# 16_ch_sample-and-hold_card.net
KiCad netlist of a schematic drawn in EAGLE
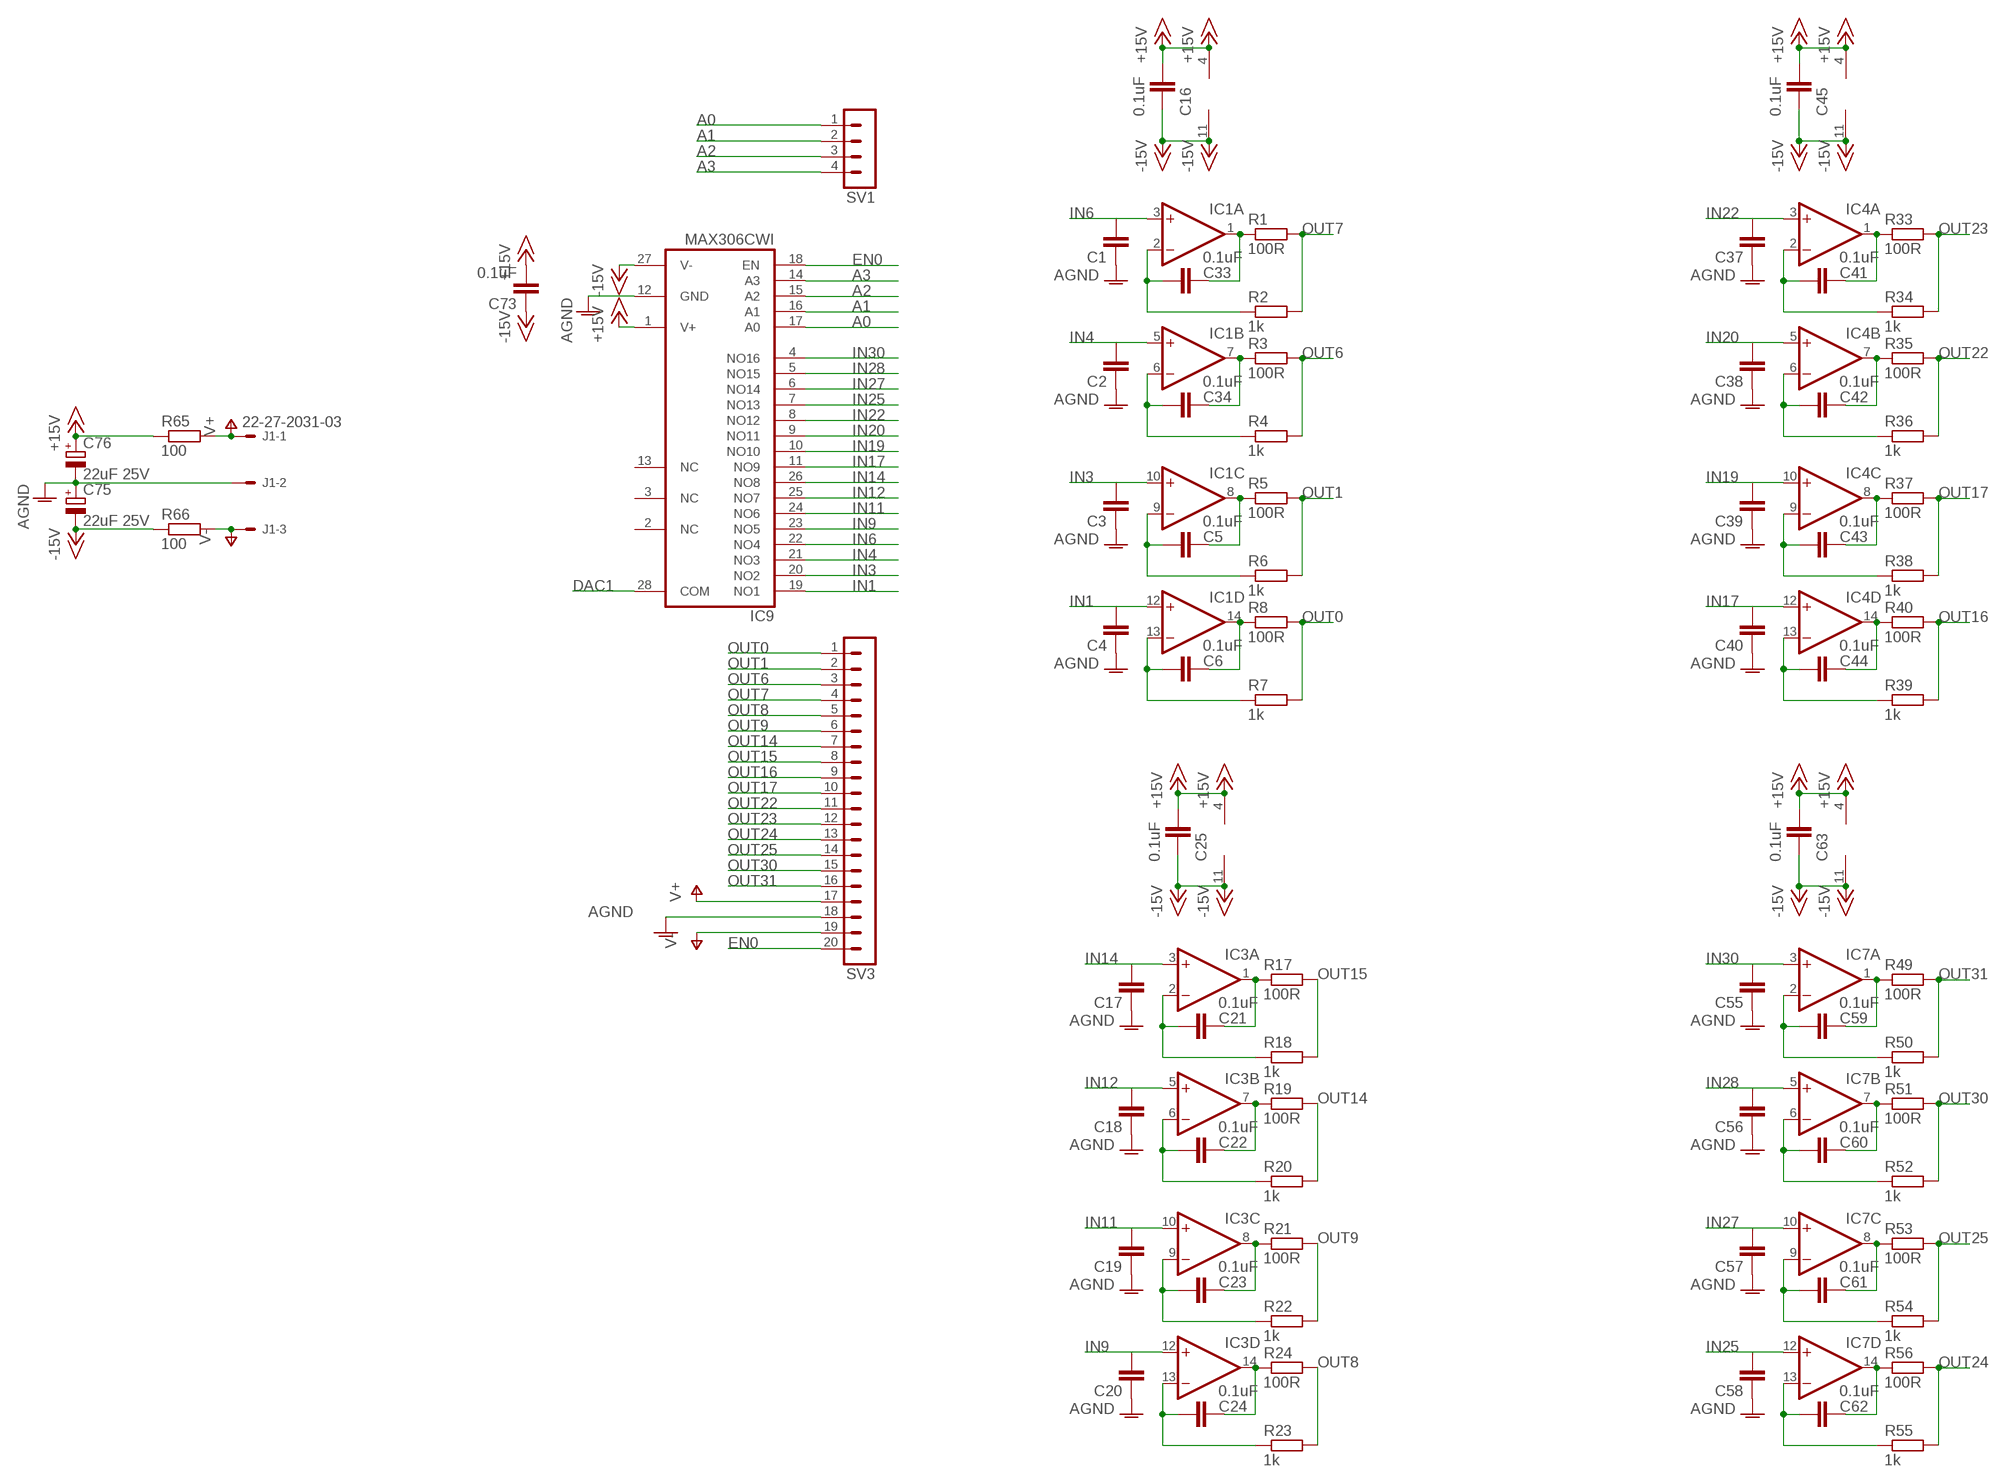
[diagram p0: schematic, sheet 1]

(export (version "E")
  (design (tool "Eeschema 10.0.6"))
  (components
    (comp (ref "C1")
      (value "C-EUC1206")
      (footprint "eagle-import:C1206")
      (libsource (lib "eagle-import") (part "C-EUC1206"))
    )
    (comp (ref "C2")
      (value "C-EUC1206")
      (footprint "eagle-import:C1206")
      (libsource (lib "eagle-import") (part "C-EUC1206"))
    )
    (comp (ref "C3")
      (value "C-EUC1206")
      (footprint "eagle-import:C1206")
      (libsource (lib "eagle-import") (part "C-EUC1206"))
    )
    (comp (ref "C4")
      (value "C-EUC1206")
      (footprint "eagle-import:C1206")
      (libsource (lib "eagle-import") (part "C-EUC1206"))
    )
    (comp (ref "C5")
      (value "0.1uF")
      (footprint "eagle-import:C0603")
      (libsource (lib "eagle-import") (part "C-EUC0603"))
    )
    (comp (ref "C6")
      (value "0.1uF")
      (footprint "eagle-import:C0603")
      (libsource (lib "eagle-import") (part "C-EUC0603"))
    )
    (comp (ref "C16")
      (value "0.1uF")
      (footprint "eagle-import:C0603")
      (libsource (lib "eagle-import") (part "C-EUC0603"))
    )
    (comp (ref "C17")
      (value "C-EUC1206")
      (footprint "eagle-import:C1206")
      (libsource (lib "eagle-import") (part "C-EUC1206"))
    )
    (comp (ref "C18")
      (value "C-EUC1206")
      (footprint "eagle-import:C1206")
      (libsource (lib "eagle-import") (part "C-EUC1206"))
    )
    (comp (ref "C19")
      (value "C-EUC1206")
      (footprint "eagle-import:C1206")
      (libsource (lib "eagle-import") (part "C-EUC1206"))
    )
    (comp (ref "C20")
      (value "C-EUC1206")
      (footprint "eagle-import:C1206")
      (libsource (lib "eagle-import") (part "C-EUC1206"))
    )
    (comp (ref "C21")
      (value "0.1uF")
      (footprint "eagle-import:C0603")
      (libsource (lib "eagle-import") (part "C-EUC0603"))
    )
    (comp (ref "C22")
      (value "0.1uF")
      (footprint "eagle-import:C0603")
      (libsource (lib "eagle-import") (part "C-EUC0603"))
    )
    (comp (ref "C23")
      (value "0.1uF")
      (footprint "eagle-import:C0603")
      (libsource (lib "eagle-import") (part "C-EUC0603"))
    )
    (comp (ref "C24")
      (value "0.1uF")
      (footprint "eagle-import:C0603")
      (libsource (lib "eagle-import") (part "C-EUC0603"))
    )
    (comp (ref "C25")
      (value "0.1uF")
      (footprint "eagle-import:C0603")
      (libsource (lib "eagle-import") (part "C-EUC0603"))
    )
    (comp (ref "C33")
      (value "0.1uF")
      (footprint "eagle-import:C0603")
      (libsource (lib "eagle-import") (part "C-EUC0603"))
    )
    (comp (ref "C34")
      (value "0.1uF")
      (footprint "eagle-import:C0603")
      (libsource (lib "eagle-import") (part "C-EUC0603"))
    )
    (comp (ref "C37")
      (value "C-EUC1206")
      (footprint "eagle-import:C1206")
      (libsource (lib "eagle-import") (part "C-EUC1206"))
    )
    (comp (ref "C38")
      (value "C-EUC1206")
      (footprint "eagle-import:C1206")
      (libsource (lib "eagle-import") (part "C-EUC1206"))
    )
    (comp (ref "C39")
      (value "C-EUC1206")
      (footprint "eagle-import:C1206")
      (libsource (lib "eagle-import") (part "C-EUC1206"))
    )
    (comp (ref "C40")
      (value "C-EUC1206")
      (footprint "eagle-import:C1206")
      (libsource (lib "eagle-import") (part "C-EUC1206"))
    )
    (comp (ref "C41")
      (value "0.1uF")
      (footprint "eagle-import:C0603")
      (libsource (lib "eagle-import") (part "C-EUC0603"))
    )
    (comp (ref "C42")
      (value "0.1uF")
      (footprint "eagle-import:C0603")
      (libsource (lib "eagle-import") (part "C-EUC0603"))
    )
    (comp (ref "C43")
      (value "0.1uF")
      (footprint "eagle-import:C0603")
      (libsource (lib "eagle-import") (part "C-EUC0603"))
    )
    (comp (ref "C44")
      (value "0.1uF")
      (footprint "eagle-import:C0603")
      (libsource (lib "eagle-import") (part "C-EUC0603"))
    )
    (comp (ref "C45")
      (value "0.1uF")
      (footprint "eagle-import:C0603")
      (libsource (lib "eagle-import") (part "C-EUC0603"))
    )
    (comp (ref "C55")
      (value "C-EUC1206")
      (footprint "eagle-import:C1206")
      (libsource (lib "eagle-import") (part "C-EUC1206"))
    )
    (comp (ref "C56")
      (value "C-EUC1206")
      (footprint "eagle-import:C1206")
      (libsource (lib "eagle-import") (part "C-EUC1206"))
    )
    (comp (ref "C57")
      (value "C-EUC1206")
      (footprint "eagle-import:C1206")
      (libsource (lib "eagle-import") (part "C-EUC1206"))
    )
    (comp (ref "C58")
      (value "C-EUC1206")
      (footprint "eagle-import:C1206")
      (libsource (lib "eagle-import") (part "C-EUC1206"))
    )
    (comp (ref "C59")
      (value "0.1uF")
      (footprint "eagle-import:C0603")
      (libsource (lib "eagle-import") (part "C-EUC0603"))
    )
    (comp (ref "C60")
      (value "0.1uF")
      (footprint "eagle-import:C0603")
      (libsource (lib "eagle-import") (part "C-EUC0603"))
    )
    (comp (ref "C61")
      (value "0.1uF")
      (footprint "eagle-import:C0603")
      (libsource (lib "eagle-import") (part "C-EUC0603"))
    )
    (comp (ref "C62")
      (value "0.1uF")
      (footprint "eagle-import:C0603")
      (libsource (lib "eagle-import") (part "C-EUC0603"))
    )
    (comp (ref "C63")
      (value "0.1uF")
      (footprint "eagle-import:C0603")
      (libsource (lib "eagle-import") (part "C-EUC0603"))
    )
    (comp (ref "C73")
      (value "0.1uF")
      (footprint "eagle-import:C0603")
      (libsource (lib "eagle-import") (part "C-EUC0603"))
    )
    (comp (ref "C75")
      (value "22uF 25V")
      (footprint "eagle-import:E2-5")
      (libsource (lib "eagle-import") (part "CPOL-EUE2-5"))
    )
    (comp (ref "C76")
      (value "22uF 25V")
      (footprint "eagle-import:E2-5")
      (libsource (lib "eagle-import") (part "CPOL-EUE2-5"))
    )
    (comp (ref "IC1")
      (value "TL074D")
      (footprint "eagle-import:SO14")
      (libsource (lib "eagle-import") (part "TL074D"))
    )
    (comp (ref "IC3")
      (value "TL074D")
      (footprint "eagle-import:SO14")
      (libsource (lib "eagle-import") (part "TL074D"))
    )
    (comp (ref "IC4")
      (value "TL074D")
      (footprint "eagle-import:SO14")
      (libsource (lib "eagle-import") (part "TL074D"))
    )
    (comp (ref "IC7")
      (value "TL074D")
      (footprint "eagle-import:SO14")
      (libsource (lib "eagle-import") (part "TL074D"))
    )
    (comp (ref "IC9")
      (value "MAX306CWI")
      (footprint "eagle-import:SO28L")
      (fields (field (name "MF") "MAXIM"))
      (libsource (lib "eagle-import") (part "MAX306CWI"))
    )
    (comp (ref "J1")
      (value "22-27-2031-03")
      (footprint "eagle-import:6410-03")
      (libsource (lib "eagle-import") (part "22-?-0327-2031"))
    )
    (comp (ref "R1")
      (value "100R")
      (footprint "eagle-import:R0603")
      (libsource (lib "eagle-import") (part "R-EU_R0603"))
    )
    (comp (ref "R2")
      (value "1k")
      (footprint "eagle-import:R0603")
      (libsource (lib "eagle-import") (part "R-EU_R0603"))
    )
    (comp (ref "R3")
      (value "100R")
      (footprint "eagle-import:R0603")
      (libsource (lib "eagle-import") (part "R-EU_R0603"))
    )
    (comp (ref "R4")
      (value "1k")
      (footprint "eagle-import:R0603")
      (libsource (lib "eagle-import") (part "R-EU_R0603"))
    )
    (comp (ref "R5")
      (value "100R")
      (footprint "eagle-import:R0603")
      (libsource (lib "eagle-import") (part "R-EU_R0603"))
    )
    (comp (ref "R6")
      (value "1k")
      (footprint "eagle-import:R0603")
      (libsource (lib "eagle-import") (part "R-EU_R0603"))
    )
    (comp (ref "R7")
      (value "1k")
      (footprint "eagle-import:R0603")
      (libsource (lib "eagle-import") (part "R-EU_R0603"))
    )
    (comp (ref "R8")
      (value "100R")
      (footprint "eagle-import:R0603")
      (libsource (lib "eagle-import") (part "R-EU_R0603"))
    )
    (comp (ref "R17")
      (value "100R")
      (footprint "eagle-import:R0603")
      (libsource (lib "eagle-import") (part "R-EU_R0603"))
    )
    (comp (ref "R18")
      (value "1k")
      (footprint "eagle-import:R0603")
      (libsource (lib "eagle-import") (part "R-EU_R0603"))
    )
    (comp (ref "R19")
      (value "100R")
      (footprint "eagle-import:R0603")
      (libsource (lib "eagle-import") (part "R-EU_R0603"))
    )
    (comp (ref "R20")
      (value "1k")
      (footprint "eagle-import:R0603")
      (libsource (lib "eagle-import") (part "R-EU_R0603"))
    )
    (comp (ref "R21")
      (value "100R")
      (footprint "eagle-import:R0603")
      (libsource (lib "eagle-import") (part "R-EU_R0603"))
    )
    (comp (ref "R22")
      (value "1k")
      (footprint "eagle-import:R0603")
      (libsource (lib "eagle-import") (part "R-EU_R0603"))
    )
    (comp (ref "R23")
      (value "1k")
      (footprint "eagle-import:R0603")
      (libsource (lib "eagle-import") (part "R-EU_R0603"))
    )
    (comp (ref "R24")
      (value "100R")
      (footprint "eagle-import:R0603")
      (libsource (lib "eagle-import") (part "R-EU_R0603"))
    )
    (comp (ref "R33")
      (value "100R")
      (footprint "eagle-import:R0603")
      (libsource (lib "eagle-import") (part "R-EU_R0603"))
    )
    (comp (ref "R34")
      (value "1k")
      (footprint "eagle-import:R0603")
      (libsource (lib "eagle-import") (part "R-EU_R0603"))
    )
    (comp (ref "R35")
      (value "100R")
      (footprint "eagle-import:R0603")
      (libsource (lib "eagle-import") (part "R-EU_R0603"))
    )
    (comp (ref "R36")
      (value "1k")
      (footprint "eagle-import:R0603")
      (libsource (lib "eagle-import") (part "R-EU_R0603"))
    )
    (comp (ref "R37")
      (value "100R")
      (footprint "eagle-import:R0603")
      (libsource (lib "eagle-import") (part "R-EU_R0603"))
    )
    (comp (ref "R38")
      (value "1k")
      (footprint "eagle-import:R0603")
      (libsource (lib "eagle-import") (part "R-EU_R0603"))
    )
    (comp (ref "R39")
      (value "1k")
      (footprint "eagle-import:R0603")
      (libsource (lib "eagle-import") (part "R-EU_R0603"))
    )
    (comp (ref "R40")
      (value "100R")
      (footprint "eagle-import:R0603")
      (libsource (lib "eagle-import") (part "R-EU_R0603"))
    )
    (comp (ref "R49")
      (value "100R")
      (footprint "eagle-import:R0603")
      (libsource (lib "eagle-import") (part "R-EU_R0603"))
    )
    (comp (ref "R50")
      (value "1k")
      (footprint "eagle-import:R0603")
      (libsource (lib "eagle-import") (part "R-EU_R0603"))
    )
    (comp (ref "R51")
      (value "100R")
      (footprint "eagle-import:R0603")
      (libsource (lib "eagle-import") (part "R-EU_R0603"))
    )
    (comp (ref "R52")
      (value "1k")
      (footprint "eagle-import:R0603")
      (libsource (lib "eagle-import") (part "R-EU_R0603"))
    )
    (comp (ref "R53")
      (value "100R")
      (footprint "eagle-import:R0603")
      (libsource (lib "eagle-import") (part "R-EU_R0603"))
    )
    (comp (ref "R54")
      (value "1k")
      (footprint "eagle-import:R0603")
      (libsource (lib "eagle-import") (part "R-EU_R0603"))
    )
    (comp (ref "R55")
      (value "1k")
      (footprint "eagle-import:R0603")
      (libsource (lib "eagle-import") (part "R-EU_R0603"))
    )
    (comp (ref "R56")
      (value "100R")
      (footprint "eagle-import:R0603")
      (libsource (lib "eagle-import") (part "R-EU_R0603"))
    )
    (comp (ref "R65")
      (value "100")
      (footprint "eagle-import:0207_7")
      (libsource (lib "eagle-import") (part "R-EU_0207/7"))
    )
    (comp (ref "R66")
      (value "100")
      (footprint "eagle-import:0207_7")
      (libsource (lib "eagle-import") (part "R-EU_0207/7"))
    )
    (comp (ref "SV1")
      (value "MA04-1")
      (footprint "eagle-import:MA04-1")
      (libsource (lib "eagle-import") (part "MA04-1"))
    )
    (comp (ref "SV3")
      (value "MA20-1")
      (footprint "eagle-import:MA20-1")
      (libsource (lib "eagle-import") (part "MA20-1"))
    )
  )
  (nets
    (net (code "1") (name "+15V") (class "Default")
      (node (ref "C16") (pin "1") (pinfunction "1_1") (pintype "passive"))
      (node (ref "C25") (pin "1") (pinfunction "1_1") (pintype "passive"))
      (node (ref "C45") (pin "1") (pinfunction "1_1") (pintype "passive"))
      (node (ref "C63") (pin "1") (pinfunction "1_1") (pintype "passive"))
      (node (ref "C73") (pin "2") (pinfunction "2_2") (pintype "passive"))
      (node (ref "C76") (pin "+") (pinfunction "+_+") (pintype "passive"))
      (node (ref "IC1") (pin "4") (pinfunction "V+_4") (pintype "power_in"))
      (node (ref "IC3") (pin "4") (pinfunction "V+_4") (pintype "power_in"))
      (node (ref "IC4") (pin "4") (pinfunction "V+_4") (pintype "power_in"))
      (node (ref "IC7") (pin "4") (pinfunction "V+_4") (pintype "power_in"))
      (node (ref "IC9") (pin "1") (pinfunction "V+_1") (pintype "power_in"))
      (node (ref "R65") (pin "1") (pinfunction "1_1") (pintype "passive"))
    )
    (net (code "2") (name "-15V") (class "Default")
      (node (ref "C16") (pin "2") (pinfunction "2_2") (pintype "passive"))
      (node (ref "C25") (pin "2") (pinfunction "2_2") (pintype "passive"))
      (node (ref "C45") (pin "2") (pinfunction "2_2") (pintype "passive"))
      (node (ref "C63") (pin "2") (pinfunction "2_2") (pintype "passive"))
      (node (ref "C73") (pin "1") (pinfunction "1_1") (pintype "passive"))
      (node (ref "C75") (pin "-") (pinfunction "-_-") (pintype "passive"))
      (node (ref "IC1") (pin "11") (pinfunction "V-_11") (pintype "power_in"))
      (node (ref "IC3") (pin "11") (pinfunction "V-_11") (pintype "power_in"))
      (node (ref "IC4") (pin "11") (pinfunction "V-_11") (pintype "power_in"))
      (node (ref "IC7") (pin "11") (pinfunction "V-_11") (pintype "power_in"))
      (node (ref "IC9") (pin "27") (pinfunction "V-_27") (pintype "power_in"))
      (node (ref "R66") (pin "1") (pinfunction "1_1") (pintype "passive"))
    )
    (net (code "3") (name "/A0") (class "Default")
      (node (ref "IC9") (pin "17") (pinfunction "A0_17") (pintype "input"))
      (node (ref "SV1") (pin "1") (pinfunction "1_1") (pintype "passive"))
    )
    (net (code "4") (name "/A1") (class "Default")
      (node (ref "IC9") (pin "16") (pinfunction "A1_16") (pintype "input"))
      (node (ref "SV1") (pin "2") (pinfunction "2_2") (pintype "passive"))
    )
    (net (code "5") (name "/A2") (class "Default")
      (node (ref "IC9") (pin "15") (pinfunction "A2_15") (pintype "input"))
      (node (ref "SV1") (pin "3") (pinfunction "3_3") (pintype "passive"))
    )
    (net (code "6") (name "/A3") (class "Default")
      (node (ref "IC9") (pin "14") (pinfunction "A3_14") (pintype "input"))
      (node (ref "SV1") (pin "4") (pinfunction "4_4") (pintype "passive"))
    )
    (net (code "7") (name "/DAC1") (class "Default")
      (node (ref "IC9") (pin "28") (pinfunction "COM_28") (pintype "passive"))
    )
    (net (code "8") (name "/EN0") (class "Default")
      (node (ref "IC9") (pin "18") (pinfunction "EN_18") (pintype "input"))
      (node (ref "SV3") (pin "20") (pinfunction "20_20") (pintype "passive"))
    )
    (net (code "9") (name "/IN1") (class "Default")
      (node (ref "C4") (pin "2") (pinfunction "2_2") (pintype "passive"))
      (node (ref "IC1") (pin "12") (pinfunction "+IN_12") (pintype "input"))
      (node (ref "IC9") (pin "19") (pinfunction "NO1_19") (pintype "passive"))
    )
    (net (code "10") (name "/IN3") (class "Default")
      (node (ref "C3") (pin "2") (pinfunction "2_2") (pintype "passive"))
      (node (ref "IC1") (pin "10") (pinfunction "+IN_10") (pintype "input"))
      (node (ref "IC9") (pin "20") (pinfunction "NO2_20") (pintype "passive"))
    )
    (net (code "11") (name "/IN4") (class "Default")
      (node (ref "C2") (pin "2") (pinfunction "2_2") (pintype "passive"))
      (node (ref "IC1") (pin "5") (pinfunction "+IN_5") (pintype "input"))
      (node (ref "IC9") (pin "21") (pinfunction "NO3_21") (pintype "passive"))
    )
    (net (code "12") (name "/IN6") (class "Default")
      (node (ref "C1") (pin "2") (pinfunction "2_2") (pintype "passive"))
      (node (ref "IC1") (pin "3") (pinfunction "+IN_3") (pintype "input"))
      (node (ref "IC9") (pin "22") (pinfunction "NO4_22") (pintype "passive"))
    )
    (net (code "13") (name "/IN9") (class "Default")
      (node (ref "C20") (pin "2") (pinfunction "2_2") (pintype "passive"))
      (node (ref "IC3") (pin "12") (pinfunction "+IN_12") (pintype "input"))
      (node (ref "IC9") (pin "23") (pinfunction "NO5_23") (pintype "passive"))
    )
    (net (code "14") (name "/IN11") (class "Default")
      (node (ref "C19") (pin "2") (pinfunction "2_2") (pintype "passive"))
      (node (ref "IC3") (pin "10") (pinfunction "+IN_10") (pintype "input"))
      (node (ref "IC9") (pin "24") (pinfunction "NO6_24") (pintype "passive"))
    )
    (net (code "15") (name "/IN12") (class "Default")
      (node (ref "C18") (pin "2") (pinfunction "2_2") (pintype "passive"))
      (node (ref "IC3") (pin "5") (pinfunction "+IN_5") (pintype "input"))
      (node (ref "IC9") (pin "25") (pinfunction "NO7_25") (pintype "passive"))
    )
    (net (code "16") (name "/IN14") (class "Default")
      (node (ref "C17") (pin "2") (pinfunction "2_2") (pintype "passive"))
      (node (ref "IC3") (pin "3") (pinfunction "+IN_3") (pintype "input"))
      (node (ref "IC9") (pin "26") (pinfunction "NO8_26") (pintype "passive"))
    )
    (net (code "17") (name "/IN17") (class "Default")
      (node (ref "C40") (pin "2") (pinfunction "2_2") (pintype "passive"))
      (node (ref "IC4") (pin "12") (pinfunction "+IN_12") (pintype "input"))
      (node (ref "IC9") (pin "11") (pinfunction "NO9_11") (pintype "passive"))
    )
    (net (code "18") (name "/IN19") (class "Default")
      (node (ref "C39") (pin "2") (pinfunction "2_2") (pintype "passive"))
      (node (ref "IC4") (pin "10") (pinfunction "+IN_10") (pintype "input"))
      (node (ref "IC9") (pin "10") (pinfunction "NO10_10") (pintype "passive"))
    )
    (net (code "19") (name "/IN20") (class "Default")
      (node (ref "C38") (pin "2") (pinfunction "2_2") (pintype "passive"))
      (node (ref "IC4") (pin "5") (pinfunction "+IN_5") (pintype "input"))
      (node (ref "IC9") (pin "9") (pinfunction "NO11_9") (pintype "passive"))
    )
    (net (code "20") (name "/IN22") (class "Default")
      (node (ref "C37") (pin "2") (pinfunction "2_2") (pintype "passive"))
      (node (ref "IC4") (pin "3") (pinfunction "+IN_3") (pintype "input"))
      (node (ref "IC9") (pin "8") (pinfunction "NO12_8") (pintype "passive"))
    )
    (net (code "21") (name "/IN25") (class "Default")
      (node (ref "C58") (pin "2") (pinfunction "2_2") (pintype "passive"))
      (node (ref "IC7") (pin "12") (pinfunction "+IN_12") (pintype "input"))
      (node (ref "IC9") (pin "7") (pinfunction "NO13_7") (pintype "passive"))
    )
    (net (code "22") (name "/IN27") (class "Default")
      (node (ref "C57") (pin "2") (pinfunction "2_2") (pintype "passive"))
      (node (ref "IC7") (pin "10") (pinfunction "+IN_10") (pintype "input"))
      (node (ref "IC9") (pin "6") (pinfunction "NO14_6") (pintype "passive"))
    )
    (net (code "23") (name "/IN28") (class "Default")
      (node (ref "C56") (pin "2") (pinfunction "2_2") (pintype "passive"))
      (node (ref "IC7") (pin "5") (pinfunction "+IN_5") (pintype "input"))
      (node (ref "IC9") (pin "5") (pinfunction "NO15_5") (pintype "passive"))
    )
    (net (code "24") (name "/IN30") (class "Default")
      (node (ref "C55") (pin "2") (pinfunction "2_2") (pintype "passive"))
      (node (ref "IC7") (pin "3") (pinfunction "+IN_3") (pintype "input"))
      (node (ref "IC9") (pin "4") (pinfunction "NO16_4") (pintype "passive"))
    )
    (net (code "25") (name "/OUT0") (class "Default")
      (node (ref "R7") (pin "2") (pinfunction "2_2") (pintype "passive"))
      (node (ref "R8") (pin "2") (pinfunction "2_2") (pintype "passive"))
      (node (ref "SV3") (pin "1") (pinfunction "1_1") (pintype "passive"))
    )
    (net (code "26") (name "/OUT1") (class "Default")
      (node (ref "R5") (pin "2") (pinfunction "2_2") (pintype "passive"))
      (node (ref "R6") (pin "2") (pinfunction "2_2") (pintype "passive"))
      (node (ref "SV3") (pin "2") (pinfunction "2_2") (pintype "passive"))
    )
    (net (code "27") (name "/OUT6") (class "Default")
      (node (ref "R3") (pin "2") (pinfunction "2_2") (pintype "passive"))
      (node (ref "R4") (pin "2") (pinfunction "2_2") (pintype "passive"))
      (node (ref "SV3") (pin "3") (pinfunction "3_3") (pintype "passive"))
    )
    (net (code "28") (name "/OUT7") (class "Default")
      (node (ref "R1") (pin "2") (pinfunction "2_2") (pintype "passive"))
      (node (ref "R2") (pin "2") (pinfunction "2_2") (pintype "passive"))
      (node (ref "SV3") (pin "4") (pinfunction "4_4") (pintype "passive"))
    )
    (net (code "29") (name "/OUT8") (class "Default")
      (node (ref "R23") (pin "2") (pinfunction "2_2") (pintype "passive"))
      (node (ref "R24") (pin "2") (pinfunction "2_2") (pintype "passive"))
      (node (ref "SV3") (pin "5") (pinfunction "5_5") (pintype "passive"))
    )
    (net (code "30") (name "/OUT9") (class "Default")
      (node (ref "R21") (pin "2") (pinfunction "2_2") (pintype "passive"))
      (node (ref "R22") (pin "2") (pinfunction "2_2") (pintype "passive"))
      (node (ref "SV3") (pin "6") (pinfunction "6_6") (pintype "passive"))
    )
    (net (code "31") (name "/OUT14") (class "Default")
      (node (ref "R19") (pin "2") (pinfunction "2_2") (pintype "passive"))
      (node (ref "R20") (pin "2") (pinfunction "2_2") (pintype "passive"))
      (node (ref "SV3") (pin "7") (pinfunction "7_7") (pintype "passive"))
    )
    (net (code "32") (name "/OUT15") (class "Default")
      (node (ref "R17") (pin "2") (pinfunction "2_2") (pintype "passive"))
      (node (ref "R18") (pin "2") (pinfunction "2_2") (pintype "passive"))
      (node (ref "SV3") (pin "8") (pinfunction "8_8") (pintype "passive"))
    )
    (net (code "33") (name "/OUT16") (class "Default")
      (node (ref "R39") (pin "2") (pinfunction "2_2") (pintype "passive"))
      (node (ref "R40") (pin "2") (pinfunction "2_2") (pintype "passive"))
      (node (ref "SV3") (pin "9") (pinfunction "9_9") (pintype "passive"))
    )
    (net (code "34") (name "/OUT17") (class "Default")
      (node (ref "R37") (pin "2") (pinfunction "2_2") (pintype "passive"))
      (node (ref "R38") (pin "2") (pinfunction "2_2") (pintype "passive"))
      (node (ref "SV3") (pin "10") (pinfunction "10_10") (pintype "passive"))
    )
    (net (code "35") (name "/OUT22") (class "Default")
      (node (ref "R35") (pin "2") (pinfunction "2_2") (pintype "passive"))
      (node (ref "R36") (pin "2") (pinfunction "2_2") (pintype "passive"))
      (node (ref "SV3") (pin "11") (pinfunction "11_11") (pintype "passive"))
    )
    (net (code "36") (name "/OUT23") (class "Default")
      (node (ref "R33") (pin "2") (pinfunction "2_2") (pintype "passive"))
      (node (ref "R34") (pin "2") (pinfunction "2_2") (pintype "passive"))
      (node (ref "SV3") (pin "12") (pinfunction "12_12") (pintype "passive"))
    )
    (net (code "37") (name "/OUT24") (class "Default")
      (node (ref "R55") (pin "2") (pinfunction "2_2") (pintype "passive"))
      (node (ref "R56") (pin "2") (pinfunction "2_2") (pintype "passive"))
      (node (ref "SV3") (pin "13") (pinfunction "13_13") (pintype "passive"))
    )
    (net (code "38") (name "/OUT25") (class "Default")
      (node (ref "R53") (pin "2") (pinfunction "2_2") (pintype "passive"))
      (node (ref "R54") (pin "2") (pinfunction "2_2") (pintype "passive"))
      (node (ref "SV3") (pin "14") (pinfunction "14_14") (pintype "passive"))
    )
    (net (code "39") (name "/OUT30") (class "Default")
      (node (ref "R51") (pin "2") (pinfunction "2_2") (pintype "passive"))
      (node (ref "R52") (pin "2") (pinfunction "2_2") (pintype "passive"))
      (node (ref "SV3") (pin "15") (pinfunction "15_15") (pintype "passive"))
    )
    (net (code "40") (name "/OUT31") (class "Default")
      (node (ref "R49") (pin "2") (pinfunction "2_2") (pintype "passive"))
      (node (ref "R50") (pin "2") (pinfunction "2_2") (pintype "passive"))
      (node (ref "SV3") (pin "16") (pinfunction "16_16") (pintype "passive"))
    )
    (net (code "41") (name "AGND") (class "Default")
      (node (ref "C1") (pin "1") (pinfunction "1_1") (pintype "passive"))
      (node (ref "C17") (pin "1") (pinfunction "1_1") (pintype "passive"))
      (node (ref "C18") (pin "1") (pinfunction "1_1") (pintype "passive"))
      (node (ref "C19") (pin "1") (pinfunction "1_1") (pintype "passive"))
      (node (ref "C2") (pin "1") (pinfunction "1_1") (pintype "passive"))
      (node (ref "C20") (pin "1") (pinfunction "1_1") (pintype "passive"))
      (node (ref "C3") (pin "1") (pinfunction "1_1") (pintype "passive"))
      (node (ref "C37") (pin "1") (pinfunction "1_1") (pintype "passive"))
      (node (ref "C38") (pin "1") (pinfunction "1_1") (pintype "passive"))
      (node (ref "C39") (pin "1") (pinfunction "1_1") (pintype "passive"))
      (node (ref "C4") (pin "1") (pinfunction "1_1") (pintype "passive"))
      (node (ref "C40") (pin "1") (pinfunction "1_1") (pintype "passive"))
      (node (ref "C55") (pin "1") (pinfunction "1_1") (pintype "passive"))
      (node (ref "C56") (pin "1") (pinfunction "1_1") (pintype "passive"))
      (node (ref "C57") (pin "1") (pinfunction "1_1") (pintype "passive"))
      (node (ref "C58") (pin "1") (pinfunction "1_1") (pintype "passive"))
      (node (ref "C75") (pin "+") (pinfunction "+_+") (pintype "passive"))
      (node (ref "C76") (pin "-") (pinfunction "-_-") (pintype "passive"))
      (node (ref "IC9") (pin "12") (pinfunction "GND_12") (pintype "power_in"))
      (node (ref "J1") (pin "2") (pinfunction "S_2") (pintype "passive"))
      (node (ref "SV3") (pin "18") (pinfunction "18_18") (pintype "passive"))
    )
    (net (code "42") (name "Net-(IC1A--IN)") (class "Default")
      (node (ref "C33") (pin "2") (pinfunction "2_2") (pintype "passive"))
      (node (ref "IC1") (pin "2") (pinfunction "-IN_2") (pintype "input"))
      (node (ref "R2") (pin "1") (pinfunction "1_1") (pintype "passive"))
    )
    (net (code "43") (name "Net-(IC1A-OUT)") (class "Default")
      (node (ref "C33") (pin "1") (pinfunction "1_1") (pintype "passive"))
      (node (ref "IC1") (pin "1") (pinfunction "OUT_1") (pintype "output"))
      (node (ref "R1") (pin "1") (pinfunction "1_1") (pintype "passive"))
    )
    (net (code "44") (name "Net-(IC1B--IN)") (class "Default")
      (node (ref "C34") (pin "2") (pinfunction "2_2") (pintype "passive"))
      (node (ref "IC1") (pin "6") (pinfunction "-IN_6") (pintype "input"))
      (node (ref "R4") (pin "1") (pinfunction "1_1") (pintype "passive"))
    )
    (net (code "45") (name "Net-(IC1B-OUT)") (class "Default")
      (node (ref "C34") (pin "1") (pinfunction "1_1") (pintype "passive"))
      (node (ref "IC1") (pin "7") (pinfunction "OUT_7") (pintype "output"))
      (node (ref "R3") (pin "1") (pinfunction "1_1") (pintype "passive"))
    )
    (net (code "46") (name "Net-(IC1C--IN)") (class "Default")
      (node (ref "C5") (pin "2") (pinfunction "2_2") (pintype "passive"))
      (node (ref "IC1") (pin "9") (pinfunction "-IN_9") (pintype "input"))
      (node (ref "R6") (pin "1") (pinfunction "1_1") (pintype "passive"))
    )
    (net (code "47") (name "Net-(IC1C-OUT)") (class "Default")
      (node (ref "C5") (pin "1") (pinfunction "1_1") (pintype "passive"))
      (node (ref "IC1") (pin "8") (pinfunction "OUT_8") (pintype "output"))
      (node (ref "R5") (pin "1") (pinfunction "1_1") (pintype "passive"))
    )
    (net (code "48") (name "Net-(IC1D--IN)") (class "Default")
      (node (ref "C6") (pin "2") (pinfunction "2_2") (pintype "passive"))
      (node (ref "IC1") (pin "13") (pinfunction "-IN_13") (pintype "input"))
      (node (ref "R7") (pin "1") (pinfunction "1_1") (pintype "passive"))
    )
    (net (code "49") (name "Net-(IC1D-OUT)") (class "Default")
      (node (ref "C6") (pin "1") (pinfunction "1_1") (pintype "passive"))
      (node (ref "IC1") (pin "14") (pinfunction "OUT_14") (pintype "output"))
      (node (ref "R8") (pin "1") (pinfunction "1_1") (pintype "passive"))
    )
    (net (code "50") (name "Net-(IC3A--IN)") (class "Default")
      (node (ref "C21") (pin "2") (pinfunction "2_2") (pintype "passive"))
      (node (ref "IC3") (pin "2") (pinfunction "-IN_2") (pintype "input"))
      (node (ref "R18") (pin "1") (pinfunction "1_1") (pintype "passive"))
    )
    (net (code "51") (name "Net-(IC3A-OUT)") (class "Default")
      (node (ref "C21") (pin "1") (pinfunction "1_1") (pintype "passive"))
      (node (ref "IC3") (pin "1") (pinfunction "OUT_1") (pintype "output"))
      (node (ref "R17") (pin "1") (pinfunction "1_1") (pintype "passive"))
    )
    (net (code "52") (name "Net-(IC3B--IN)") (class "Default")
      (node (ref "C22") (pin "2") (pinfunction "2_2") (pintype "passive"))
      (node (ref "IC3") (pin "6") (pinfunction "-IN_6") (pintype "input"))
      (node (ref "R20") (pin "1") (pinfunction "1_1") (pintype "passive"))
    )
    (net (code "53") (name "Net-(IC3B-OUT)") (class "Default")
      (node (ref "C22") (pin "1") (pinfunction "1_1") (pintype "passive"))
      (node (ref "IC3") (pin "7") (pinfunction "OUT_7") (pintype "output"))
      (node (ref "R19") (pin "1") (pinfunction "1_1") (pintype "passive"))
    )
    (net (code "54") (name "Net-(IC3C--IN)") (class "Default")
      (node (ref "C23") (pin "2") (pinfunction "2_2") (pintype "passive"))
      (node (ref "IC3") (pin "9") (pinfunction "-IN_9") (pintype "input"))
      (node (ref "R22") (pin "1") (pinfunction "1_1") (pintype "passive"))
    )
    (net (code "55") (name "Net-(IC3C-OUT)") (class "Default")
      (node (ref "C23") (pin "1") (pinfunction "1_1") (pintype "passive"))
      (node (ref "IC3") (pin "8") (pinfunction "OUT_8") (pintype "output"))
      (node (ref "R21") (pin "1") (pinfunction "1_1") (pintype "passive"))
    )
    (net (code "56") (name "Net-(IC3D--IN)") (class "Default")
      (node (ref "C24") (pin "2") (pinfunction "2_2") (pintype "passive"))
      (node (ref "IC3") (pin "13") (pinfunction "-IN_13") (pintype "input"))
      (node (ref "R23") (pin "1") (pinfunction "1_1") (pintype "passive"))
    )
    (net (code "57") (name "Net-(IC3D-OUT)") (class "Default")
      (node (ref "C24") (pin "1") (pinfunction "1_1") (pintype "passive"))
      (node (ref "IC3") (pin "14") (pinfunction "OUT_14") (pintype "output"))
      (node (ref "R24") (pin "1") (pinfunction "1_1") (pintype "passive"))
    )
    (net (code "58") (name "Net-(IC4A--IN)") (class "Default")
      (node (ref "C41") (pin "2") (pinfunction "2_2") (pintype "passive"))
      (node (ref "IC4") (pin "2") (pinfunction "-IN_2") (pintype "input"))
      (node (ref "R34") (pin "1") (pinfunction "1_1") (pintype "passive"))
    )
    (net (code "59") (name "Net-(IC4A-OUT)") (class "Default")
      (node (ref "C41") (pin "1") (pinfunction "1_1") (pintype "passive"))
      (node (ref "IC4") (pin "1") (pinfunction "OUT_1") (pintype "output"))
      (node (ref "R33") (pin "1") (pinfunction "1_1") (pintype "passive"))
    )
    (net (code "60") (name "Net-(IC4B--IN)") (class "Default")
      (node (ref "C42") (pin "2") (pinfunction "2_2") (pintype "passive"))
      (node (ref "IC4") (pin "6") (pinfunction "-IN_6") (pintype "input"))
      (node (ref "R36") (pin "1") (pinfunction "1_1") (pintype "passive"))
    )
    (net (code "61") (name "Net-(IC4B-OUT)") (class "Default")
      (node (ref "C42") (pin "1") (pinfunction "1_1") (pintype "passive"))
      (node (ref "IC4") (pin "7") (pinfunction "OUT_7") (pintype "output"))
      (node (ref "R35") (pin "1") (pinfunction "1_1") (pintype "passive"))
    )
    (net (code "62") (name "Net-(IC4C--IN)") (class "Default")
      (node (ref "C43") (pin "2") (pinfunction "2_2") (pintype "passive"))
      (node (ref "IC4") (pin "9") (pinfunction "-IN_9") (pintype "input"))
      (node (ref "R38") (pin "1") (pinfunction "1_1") (pintype "passive"))
    )
    (net (code "63") (name "Net-(IC4C-OUT)") (class "Default")
      (node (ref "C43") (pin "1") (pinfunction "1_1") (pintype "passive"))
      (node (ref "IC4") (pin "8") (pinfunction "OUT_8") (pintype "output"))
      (node (ref "R37") (pin "1") (pinfunction "1_1") (pintype "passive"))
    )
    (net (code "64") (name "Net-(IC4D--IN)") (class "Default")
      (node (ref "C44") (pin "2") (pinfunction "2_2") (pintype "passive"))
      (node (ref "IC4") (pin "13") (pinfunction "-IN_13") (pintype "input"))
      (node (ref "R39") (pin "1") (pinfunction "1_1") (pintype "passive"))
    )
    (net (code "65") (name "Net-(IC4D-OUT)") (class "Default")
      (node (ref "C44") (pin "1") (pinfunction "1_1") (pintype "passive"))
      (node (ref "IC4") (pin "14") (pinfunction "OUT_14") (pintype "output"))
      (node (ref "R40") (pin "1") (pinfunction "1_1") (pintype "passive"))
    )
    (net (code "66") (name "Net-(IC7A--IN)") (class "Default")
      (node (ref "C59") (pin "2") (pinfunction "2_2") (pintype "passive"))
      (node (ref "IC7") (pin "2") (pinfunction "-IN_2") (pintype "input"))
      (node (ref "R50") (pin "1") (pinfunction "1_1") (pintype "passive"))
    )
    (net (code "67") (name "Net-(IC7A-OUT)") (class "Default")
      (node (ref "C59") (pin "1") (pinfunction "1_1") (pintype "passive"))
      (node (ref "IC7") (pin "1") (pinfunction "OUT_1") (pintype "output"))
      (node (ref "R49") (pin "1") (pinfunction "1_1") (pintype "passive"))
    )
    (net (code "68") (name "Net-(IC7B--IN)") (class "Default")
      (node (ref "C60") (pin "2") (pinfunction "2_2") (pintype "passive"))
      (node (ref "IC7") (pin "6") (pinfunction "-IN_6") (pintype "input"))
      (node (ref "R52") (pin "1") (pinfunction "1_1") (pintype "passive"))
    )
    (net (code "69") (name "Net-(IC7B-OUT)") (class "Default")
      (node (ref "C60") (pin "1") (pinfunction "1_1") (pintype "passive"))
      (node (ref "IC7") (pin "7") (pinfunction "OUT_7") (pintype "output"))
      (node (ref "R51") (pin "1") (pinfunction "1_1") (pintype "passive"))
    )
    (net (code "70") (name "Net-(IC7C--IN)") (class "Default")
      (node (ref "C61") (pin "2") (pinfunction "2_2") (pintype "passive"))
      (node (ref "IC7") (pin "9") (pinfunction "-IN_9") (pintype "input"))
      (node (ref "R54") (pin "1") (pinfunction "1_1") (pintype "passive"))
    )
    (net (code "71") (name "Net-(IC7C-OUT)") (class "Default")
      (node (ref "C61") (pin "1") (pinfunction "1_1") (pintype "passive"))
      (node (ref "IC7") (pin "8") (pinfunction "OUT_8") (pintype "output"))
      (node (ref "R53") (pin "1") (pinfunction "1_1") (pintype "passive"))
    )
    (net (code "72") (name "Net-(IC7D--IN)") (class "Default")
      (node (ref "C62") (pin "2") (pinfunction "2_2") (pintype "passive"))
      (node (ref "IC7") (pin "13") (pinfunction "-IN_13") (pintype "input"))
      (node (ref "R55") (pin "1") (pinfunction "1_1") (pintype "passive"))
    )
    (net (code "73") (name "Net-(IC7D-OUT)") (class "Default")
      (node (ref "C62") (pin "1") (pinfunction "1_1") (pintype "passive"))
      (node (ref "IC7") (pin "14") (pinfunction "OUT_14") (pintype "output"))
      (node (ref "R56") (pin "1") (pinfunction "1_1") (pintype "passive"))
    )
    (net (code "74") (name "V+") (class "Default")
      (node (ref "J1") (pin "1") (pinfunction "S_1") (pintype "passive"))
      (node (ref "R65") (pin "2") (pinfunction "2_2") (pintype "passive"))
      (node (ref "SV3") (pin "17") (pinfunction "17_17") (pintype "passive"))
    )
    (net (code "75") (name "V-") (class "Default")
      (node (ref "J1") (pin "3") (pinfunction "S_3") (pintype "passive"))
      (node (ref "R66") (pin "2") (pinfunction "2_2") (pintype "passive"))
      (node (ref "SV3") (pin "19") (pinfunction "19_19") (pintype "passive"))
    )
    (net (code "76") (name "unconnected-(IC9-NC-Pad2)") (class "Default")
      (node (ref "IC9") (pin "2") (pinfunction "NC_2") (pintype "no_connect"))
    )
    (net (code "77") (name "unconnected-(IC9-NC-Pad3)") (class "Default")
      (node (ref "IC9") (pin "3") (pinfunction "NC_3") (pintype "no_connect"))
    )
    (net (code "78") (name "unconnected-(IC9-NC-Pad13)") (class "Default")
      (node (ref "IC9") (pin "13") (pinfunction "NC_13") (pintype "no_connect"))
    )
  )
)
